# lab1_lyahovskij_USB_I2C.net
KiCad netlist of a schematic drawn in Altium Designer
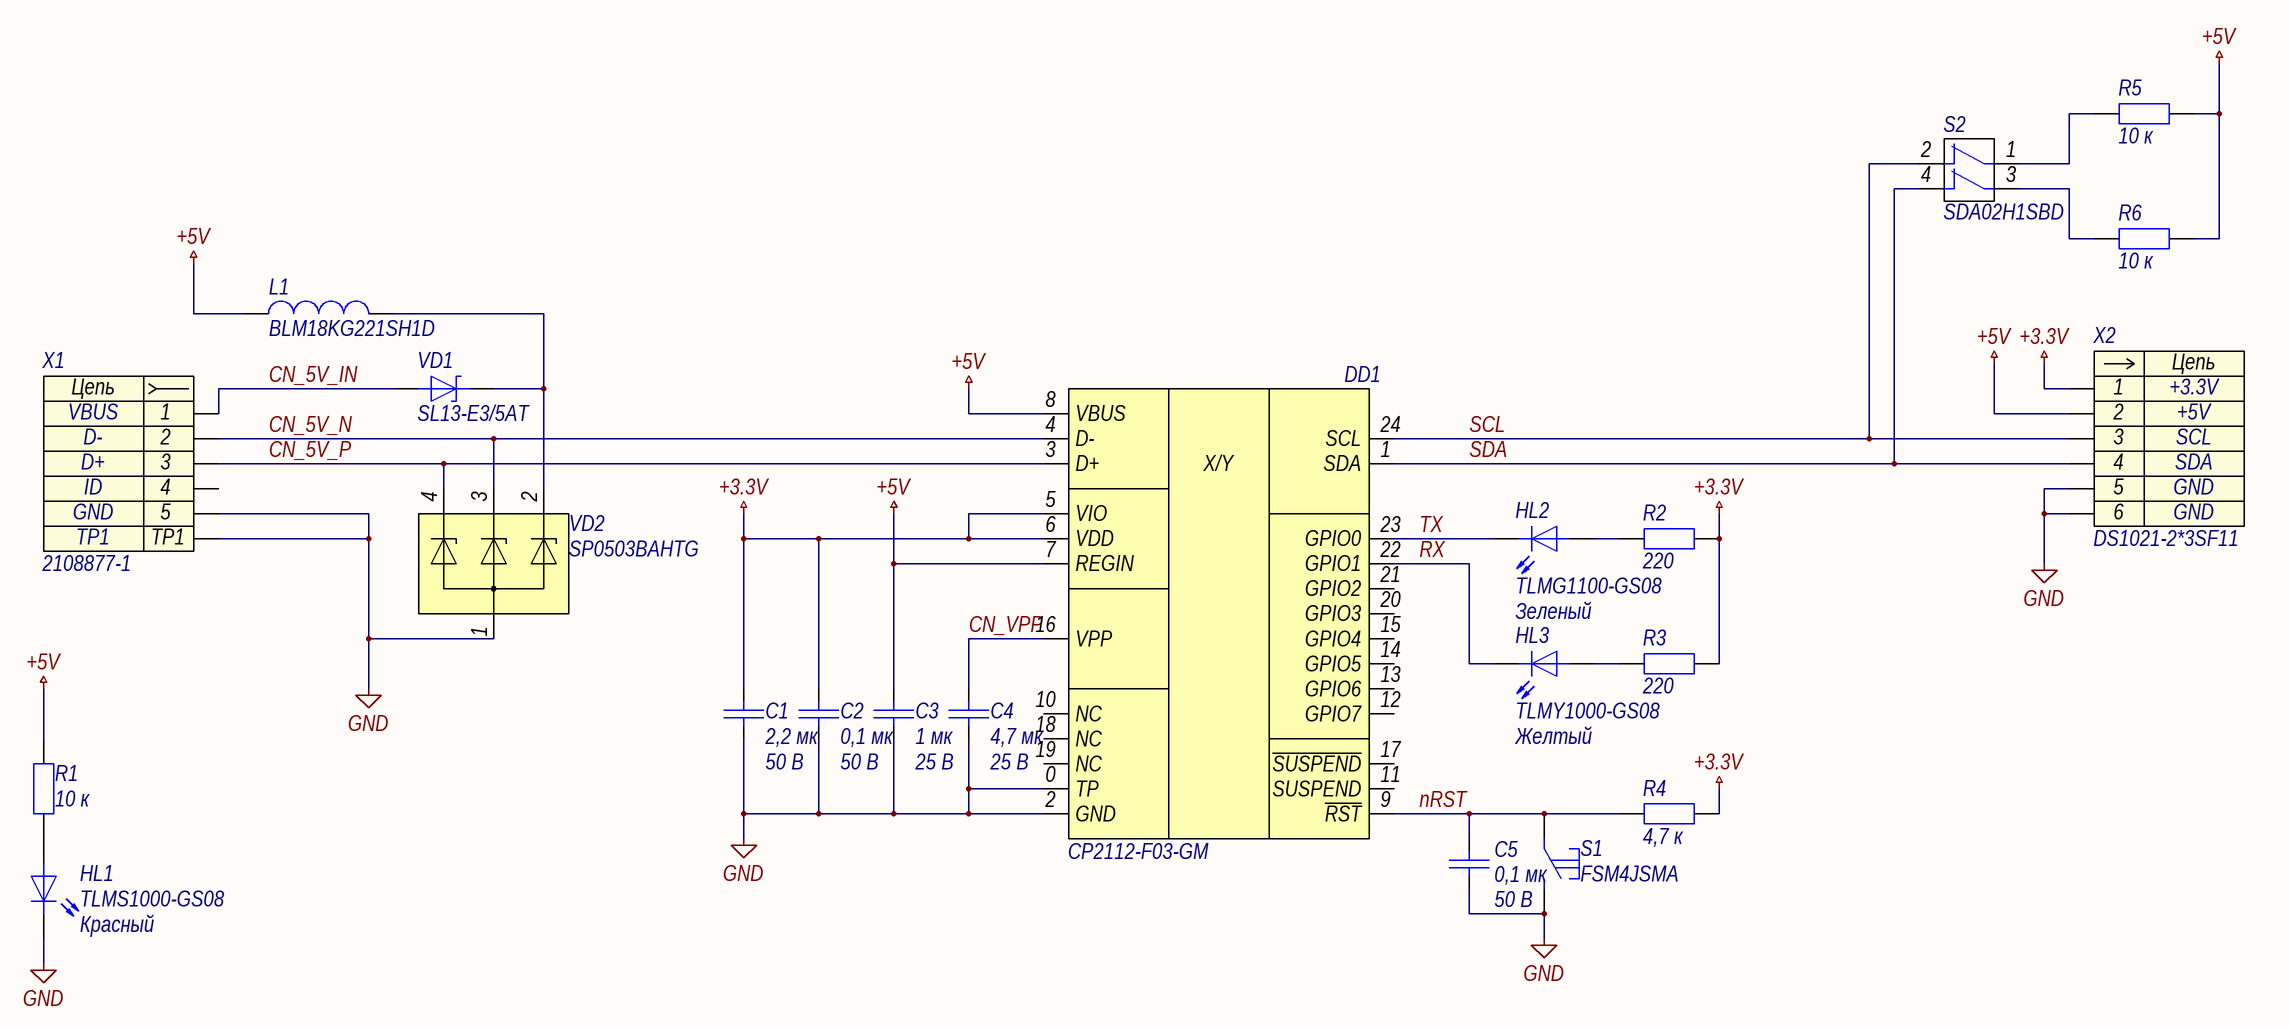
[diagram p0: lab1_lyahovskij_USB_I2C.SchDoc]

(export (version "E")
  (design (tool "Eeschema 10.0.6"))
  (components
    (comp (ref "C1")
      (value "2,2 мк")
      (footprint "C0603")
      (description "=Описание")
      (fields (field (name "НАПРЯЖЕНИЕ") "50 В"))
      (libsource (lib "Database_Students") (part "CAPACITOR-NONPOLAR"))
    )
    (comp (ref "C2")
      (value "0,1 мк")
      (footprint "C0603")
      (description "=Описание")
      (fields (field (name "НАПРЯЖЕНИЕ") "50 В"))
      (libsource (lib "Database_Students") (part "CAPACITOR-NONPOLAR"))
    )
    (comp (ref "C3")
      (value "1 мк")
      (footprint "C0603")
      (description "=Описание")
      (fields (field (name "НАПРЯЖЕНИЕ") "25 В"))
      (libsource (lib "Database_Students") (part "CAPACITOR-NONPOLAR"))
    )
    (comp (ref "C4")
      (value "4,7 мк")
      (footprint "C0603")
      (description "=Описание")
      (fields (field (name "НАПРЯЖЕНИЕ") "25 В"))
      (libsource (lib "Database_Students") (part "CAPACITOR-NONPOLAR"))
    )
    (comp (ref "C5")
      (value "0,1 мк")
      (footprint "C0603")
      (description "=Описание")
      (fields (field (name "НАПРЯЖЕНИЕ") "50 В"))
      (libsource (lib "Database_Students") (part "CAPACITOR-NONPOLAR"))
    )
    (comp (ref "DD1")
      (value "CP2112-F03-GM")
      (footprint "QFN-24-400X400X80")
      (description "=Описание")
      (libsource (lib "Database_Students") (part "CP2112-F03-GM"))
    )
    (comp (ref "HL1")
      (value "TLMS1000-GS08")
      (footprint "HL0603")
      (description "=Описание")
      (fields (field (name "COLOUR") "Красный"))
      (libsource (lib "Database_Students") (part "LED-COMMON"))
    )
    (comp (ref "HL2")
      (value "TLMG1100-GS08")
      (footprint "HL0603")
      (description "=Описание")
      (fields (field (name "COLOUR") "Зеленый"))
      (libsource (lib "Database_Students") (part "LED-COMMON"))
    )
    (comp (ref "HL3")
      (value "TLMY1000-GS08")
      (footprint "HL0603")
      (description "=Описание")
      (fields (field (name "COLOUR") "Желтый"))
      (libsource (lib "Database_Students") (part "LED-COMMON"))
    )
    (comp (ref "L1")
      (value "BLM18KG221SH1D")
      (footprint "BLM-2-0603")
      (description "=Описание")
      (libsource (lib "Database_Students") (part "FERRITE-BEAD"))
    )
    (comp (ref "R1")
      (value "10 к")
      (footprint "R0603")
      (description "=Описание")
      (libsource (lib "Database_Students") (part "R-COMMON"))
    )
    (comp (ref "R2")
      (value "220")
      (footprint "R0603")
      (description "=Описание")
      (libsource (lib "Database_Students") (part "R-COMMON"))
    )
    (comp (ref "R3")
      (value "220")
      (footprint "R0603")
      (description "=Описание")
      (libsource (lib "Database_Students") (part "R-COMMON"))
    )
    (comp (ref "R4")
      (value "4,7 к")
      (footprint "R0603")
      (description "=Описание")
      (libsource (lib "Database_Students") (part "R-COMMON"))
    )
    (comp (ref "R5")
      (value "10 к")
      (footprint "R0603")
      (description "=Описание")
      (libsource (lib "Database_Students") (part "R-COMMON"))
    )
    (comp (ref "R6")
      (value "10 к")
      (footprint "R0603")
      (description "=Описание")
      (libsource (lib "Database_Students") (part "R-COMMON"))
    )
    (comp (ref "S1")
      (value "FSM4JSMA")
      (footprint "FSM4JSMA")
      (description "=Описание")
      (libsource (lib "Database_Students") (part "SWITCH-01"))
    )
    (comp (ref "S2")
      (value "SDA02H1SBD")
      (footprint "SDA02H1SBD")
      (description "=Описание")
      (libsource (lib "Database_Students") (part "SWITCH-4C"))
    )
    (comp (ref "VD1")
      (value "SL13-E3/5AT")
      (footprint "DO-214AC")
      (description "=Описание")
      (libsource (lib "Database_Students") (part "DIODE-SCHOTTKY"))
    )
    (comp (ref "VD2")
      (value "SP0503BAHTG")
      (footprint "SOT-143-4")
      (description "=Описание")
      (libsource (lib "Database_Students") (part "SP0503BAHTG"))
    )
    (comp (ref "X1")
      (value "2108877-1")
      (footprint "2108877-1")
      (description "=Описание")
      (libsource (lib "Database_Students") (part "HEADER-5-TP1-SCT"))
    )
    (comp (ref "X2")
      (value "DS1021-2*3SF11")
      (footprint "DS1021-2X3SF11")
      (description "=Описание")
      (libsource (lib "Database_Students") (part "HEADER-6-PLG"))
    )
  )
  (nets
    (net (code "1") (name "+3.3V") (class "Default")
      (node (ref "C1") (pin "1") (pinfunction "1_1") (pintype "passive"))
      (node (ref "C2") (pin "1") (pinfunction "1_1") (pintype "passive"))
      (node (ref "DD1") (pin "5") (pinfunction "VIO_5") (pintype "passive"))
      (node (ref "DD1") (pin "6") (pinfunction "VDD_6") (pintype "passive"))
      (node (ref "R2") (pin "2") (pinfunction "2_2") (pintype "passive"))
      (node (ref "R3") (pin "2") (pinfunction "2_2") (pintype "passive"))
      (node (ref "R4") (pin "1") (pinfunction "1_1") (pintype "passive"))
      (node (ref "X2") (pin "1") (pinfunction "1_1") (pintype "passive"))
    )
    (net (code "2") (name "+5V") (class "Default")
      (node (ref "C3") (pin "1") (pinfunction "1_1") (pintype "passive"))
      (node (ref "DD1") (pin "7") (pinfunction "REGIN_7") (pintype "passive"))
      (node (ref "DD1") (pin "8") (pinfunction "VBUS_8") (pintype "passive"))
      (node (ref "L1") (pin "2") (pinfunction "2_2") (pintype "passive"))
      (node (ref "R1") (pin "2") (pinfunction "2_2") (pintype "passive"))
      (node (ref "R5") (pin "2") (pinfunction "2_2") (pintype "passive"))
      (node (ref "R6") (pin "2") (pinfunction "2_2") (pintype "passive"))
      (node (ref "X2") (pin "2") (pinfunction "2_2") (pintype "passive"))
    )
    (net (code "3") (name "/CN_5V_IN") (class "Default")
      (node (ref "VD1") (pin "2") (pinfunction "2_2") (pintype "passive"))
      (node (ref "X1") (pin "1") (pinfunction "1_1") (pintype "passive"))
    )
    (net (code "4") (name "/CN_5V_N") (class "Default")
      (node (ref "DD1") (pin "4") (pinfunction "D-_4") (pintype "passive"))
      (node (ref "VD2") (pin "3") (pinfunction "3_3") (pintype "passive"))
      (node (ref "X1") (pin "2") (pinfunction "2_2") (pintype "passive"))
    )
    (net (code "5") (name "/CN_5V_P") (class "Default")
      (node (ref "DD1") (pin "3") (pinfunction "D+_3") (pintype "passive"))
      (node (ref "VD2") (pin "4") (pinfunction "4_4") (pintype "passive"))
      (node (ref "X1") (pin "3") (pinfunction "3_3") (pintype "passive"))
    )
    (net (code "6") (name "/CN_VPP") (class "Default")
      (node (ref "C4") (pin "1") (pinfunction "1_1") (pintype "passive"))
      (node (ref "DD1") (pin "16") (pinfunction "VPP_16") (pintype "passive"))
    )
    (net (code "7") (name "/RX") (class "Default")
      (node (ref "DD1") (pin "22") (pinfunction "GPIO1_22") (pintype "passive"))
      (node (ref "HL3") (pin "1") (pinfunction "1_1") (pintype "passive"))
    )
    (net (code "8") (name "/SCL") (class "Default")
      (node (ref "DD1") (pin "24") (pinfunction "SCL_24") (pintype "passive"))
      (node (ref "S2") (pin "2") (pinfunction "2_2") (pintype "passive"))
      (node (ref "X2") (pin "3") (pinfunction "3_3") (pintype "passive"))
    )
    (net (code "9") (name "/SDA") (class "Default")
      (node (ref "DD1") (pin "1") (pinfunction "SDA_1") (pintype "passive"))
      (node (ref "S2") (pin "4") (pinfunction "4_4") (pintype "passive"))
      (node (ref "X2") (pin "4") (pinfunction "4_4") (pintype "passive"))
    )
    (net (code "10") (name "/TX") (class "Default")
      (node (ref "DD1") (pin "23") (pinfunction "GPIO0_23") (pintype "passive"))
      (node (ref "HL2") (pin "1") (pinfunction "1_1") (pintype "passive"))
    )
    (net (code "11") (name "/nRST") (class "Default")
      (node (ref "C5") (pin "1") (pinfunction "1_1") (pintype "passive"))
      (node (ref "DD1") (pin "9") (pinfunction "~{RST}_9") (pintype "passive"))
      (node (ref "R4") (pin "2") (pinfunction "2_2") (pintype "passive"))
      (node (ref "S1") (pin "1") (pinfunction "1_1") (pintype "passive"))
    )
    (net (code "12") (name "GND") (class "Default")
      (node (ref "C1") (pin "2") (pinfunction "2_2") (pintype "passive"))
      (node (ref "C2") (pin "2") (pinfunction "2_2") (pintype "passive"))
      (node (ref "C3") (pin "2") (pinfunction "2_2") (pintype "passive"))
      (node (ref "C4") (pin "2") (pinfunction "2_2") (pintype "passive"))
      (node (ref "C5") (pin "2") (pinfunction "2_2") (pintype "passive"))
      (node (ref "DD1") (pin "0") (pinfunction "TP_0") (pintype "passive"))
      (node (ref "DD1") (pin "2") (pinfunction "GND_2") (pintype "passive"))
      (node (ref "HL1") (pin "1") (pinfunction "1_1") (pintype "passive"))
      (node (ref "S1") (pin "2") (pinfunction "2_2") (pintype "passive"))
      (node (ref "VD2") (pin "1") (pinfunction "1_1") (pintype "passive"))
      (node (ref "X1") (pin "5") (pinfunction "5_5") (pintype "passive"))
      (node (ref "X1") (pin "TP1") (pinfunction "TP1_TP1") (pintype "passive"))
      (node (ref "X2") (pin "5") (pinfunction "5_5") (pintype "passive"))
      (node (ref "X2") (pin "6") (pinfunction "6_6") (pintype "passive"))
    )
    (net (code "13") (name "Net-(HL1-Pad2)") (class "Default")
      (node (ref "HL1") (pin "2") (pinfunction "2_2") (pintype "passive"))
      (node (ref "R1") (pin "1") (pinfunction "1_1") (pintype "passive"))
    )
    (net (code "14") (name "Net-(HL2-Pad2)") (class "Default")
      (node (ref "HL2") (pin "2") (pinfunction "2_2") (pintype "passive"))
      (node (ref "R2") (pin "1") (pinfunction "1_1") (pintype "passive"))
    )
    (net (code "15") (name "Net-(HL3-Pad2)") (class "Default")
      (node (ref "HL3") (pin "2") (pinfunction "2_2") (pintype "passive"))
      (node (ref "R3") (pin "1") (pinfunction "1_1") (pintype "passive"))
    )
    (net (code "16") (name "Net-(L1-Pad1)") (class "Default")
      (node (ref "L1") (pin "1") (pinfunction "1_1") (pintype "passive"))
      (node (ref "VD1") (pin "1") (pinfunction "1_1") (pintype "passive"))
      (node (ref "VD2") (pin "2") (pinfunction "2_2") (pintype "passive"))
    )
    (net (code "17") (name "Net-(R5-Pad1)") (class "Default")
      (node (ref "R5") (pin "1") (pinfunction "1_1") (pintype "passive"))
      (node (ref "S2") (pin "1") (pinfunction "1_1") (pintype "passive"))
    )
    (net (code "18") (name "Net-(R6-Pad1)") (class "Default")
      (node (ref "R6") (pin "1") (pinfunction "1_1") (pintype "passive"))
      (node (ref "S2") (pin "3") (pinfunction "3_3") (pintype "passive"))
    )
    (net (code "19") (name "unconnected-(DD1-GPIO2-Pad21)") (class "Default")
      (node (ref "DD1") (pin "21") (pinfunction "GPIO2_21") (pintype "passive"))
    )
    (net (code "20") (name "unconnected-(DD1-GPIO3-Pad20)") (class "Default")
      (node (ref "DD1") (pin "20") (pinfunction "GPIO3_20") (pintype "passive"))
    )
    (net (code "21") (name "unconnected-(DD1-GPIO4-Pad15)") (class "Default")
      (node (ref "DD1") (pin "15") (pinfunction "GPIO4_15") (pintype "passive"))
    )
    (net (code "22") (name "unconnected-(DD1-GPIO5-Pad14)") (class "Default")
      (node (ref "DD1") (pin "14") (pinfunction "GPIO5_14") (pintype "passive"))
    )
    (net (code "23") (name "unconnected-(DD1-GPIO6-Pad13)") (class "Default")
      (node (ref "DD1") (pin "13") (pinfunction "GPIO6_13") (pintype "passive"))
    )
    (net (code "24") (name "unconnected-(DD1-GPIO7-Pad12)") (class "Default")
      (node (ref "DD1") (pin "12") (pinfunction "GPIO7_12") (pintype "passive"))
    )
    (net (code "25") (name "unconnected-(DD1-NC-Pad10)") (class "Default")
      (node (ref "DD1") (pin "10") (pinfunction "NC_10") (pintype "passive"))
    )
    (net (code "26") (name "unconnected-(DD1-NC-Pad18)") (class "Default")
      (node (ref "DD1") (pin "18") (pinfunction "NC_18") (pintype "passive"))
    )
    (net (code "27") (name "unconnected-(DD1-NC-Pad19)") (class "Default")
      (node (ref "DD1") (pin "19") (pinfunction "NC_19") (pintype "passive"))
    )
    (net (code "28") (name "unconnected-(DD1-SUSPEND-Pad11)") (class "Default")
      (node (ref "DD1") (pin "11") (pinfunction "SUSPEND_11") (pintype "passive"))
    )
    (net (code "29") (name "unconnected-(DD1-~{SUSPEND}-Pad17)") (class "Default")
      (node (ref "DD1") (pin "17") (pinfunction "~{SUSPEND}_17") (pintype "passive"))
    )
    (net (code "30") (name "unconnected-(X1-Pad4)") (class "Default")
      (node (ref "X1") (pin "4") (pinfunction "4_4") (pintype "passive"))
    )
  )
)
